# CheeseCake_1stAnn_SP.net
KiCad netlist of a schematic drawn in EasyEDA Pro
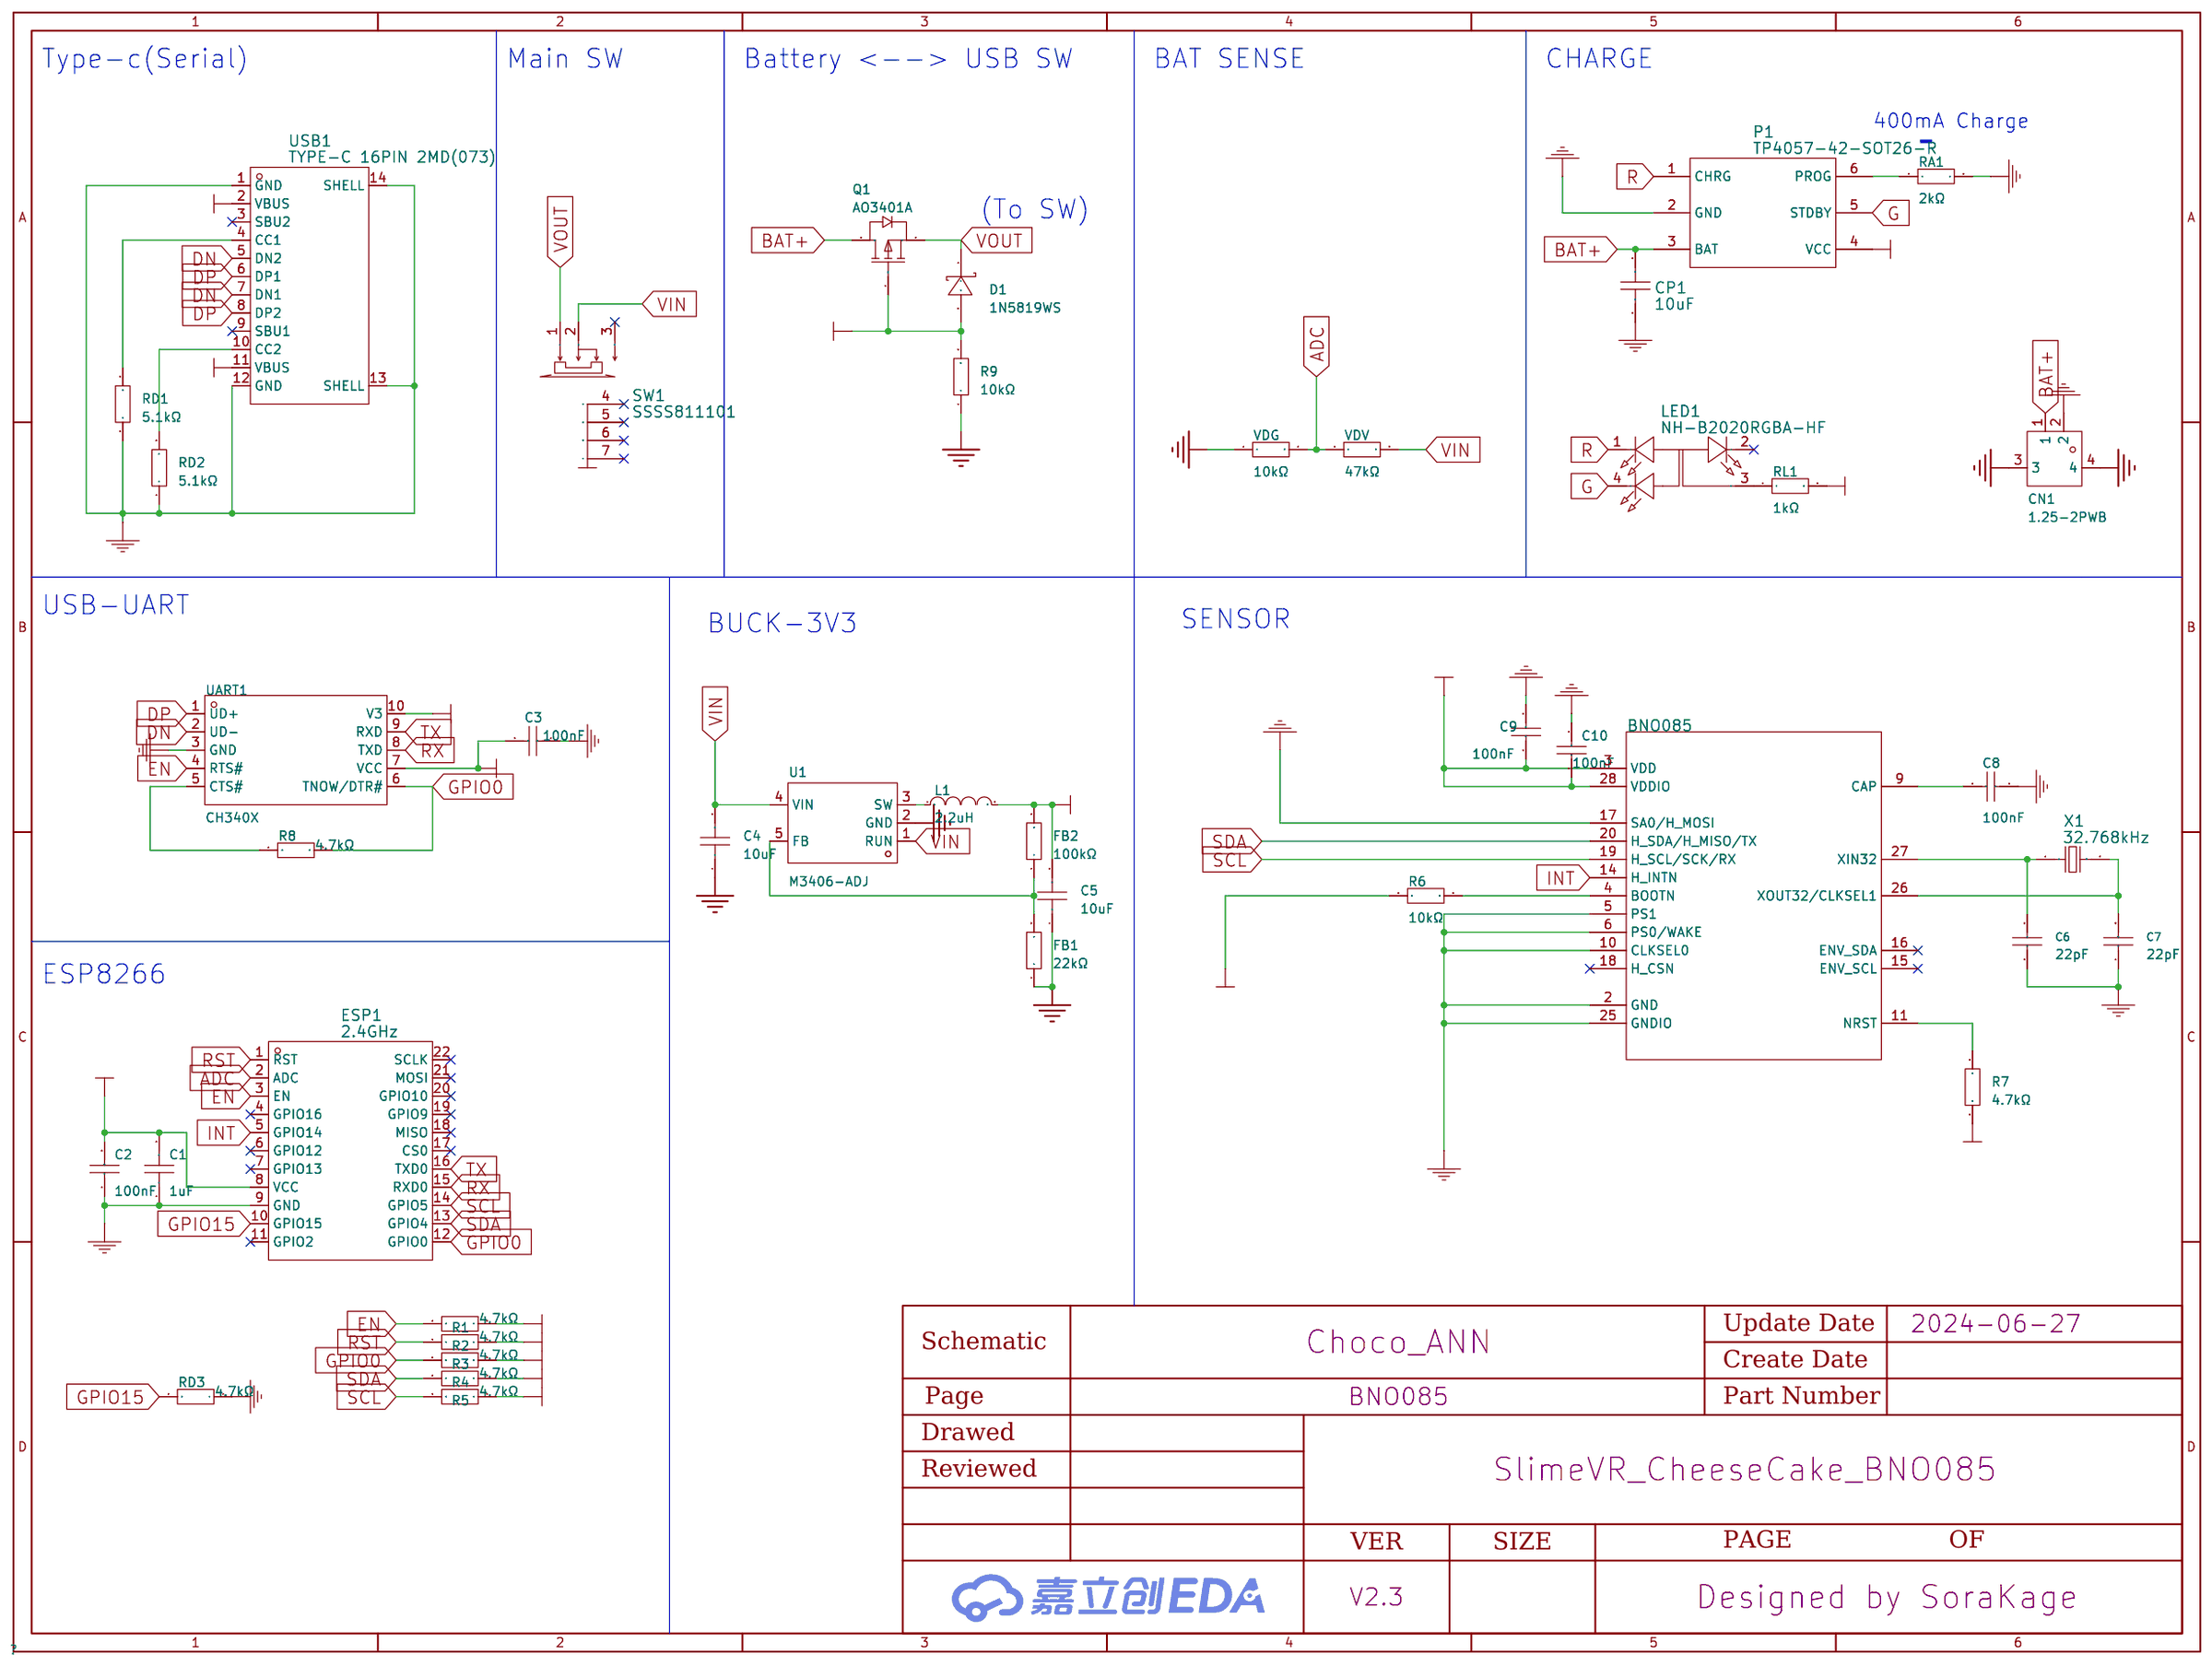
[diagram p0: schematic sheet]

(export (version "E")
  (design (tool "Eeschema 10.0.6"))
  (components
    (comp (ref "BNO085")
      (value "BNO080")
      (fields (field (name "Manufacturer Part") "BNO085") (field (name "Manufacturer") "Hillcrest"))
      (libsource (lib "easyedapro") (part "BNO080"))
    )
    (comp (ref "C1")
      (value "1uF")
      (footprint "easyedapro:C0402")
      (description "容值:1uF;精度:±10%;额定电压:25V;材质(温度系数):X5R;")
      (fields
        (field (name "Manufacturer Part") "CL05A105KA5NQNC")
        (field (name "Manufacturer") "SAMSUNG(三星)")
      )
      (libsource (lib "easyedapro") (part "CL05A105KA5NQNC"))
    )
    (comp (ref "C2")
      (value "100nF")
      (footprint "easyedapro:C0402")
      (description "容值:100nF;精度:±10%;额定电压:16V;材质(温度系数):X7R;")
      (fields
        (field (name "Manufacturer Part") "CL05B104KO5NNNC")
        (field (name "Manufacturer") "SAMSUNG(三星)")
      )
      (libsource (lib "easyedapro") (part "CL05B104KO5NNNC"))
    )
    (comp (ref "C3")
      (value "100nF")
      (footprint "easyedapro:C0402")
      (description "容值:100nF;精度:±10%;额定电压:16V;材质(温度系数):X7R;")
      (fields
        (field (name "Manufacturer Part") "CL05B104KO5NNNC")
        (field (name "Manufacturer") "SAMSUNG(三星)")
      )
      (libsource (lib "easyedapro") (part "CL05B104KO5NNNC"))
    )
    (comp (ref "C4")
      (value "10uF")
      (footprint "easyedapro:C0603")
      (description "容值:10uF;精度:±10%;额定电压:10V;材质(温度系数):X5R;")
      (fields
        (field (name "Manufacturer Part") "CL10A106KP8NNNC")
        (field (name "Manufacturer") "SAMSUNG(三星)")
      )
      (libsource (lib "easyedapro") (part "CL10A106KP8NNNC"))
    )
    (comp (ref "C5")
      (value "10uF")
      (footprint "easyedapro:C0603")
      (description "容值:10uF;精度:±10%;额定电压:10V;材质(温度系数):X5R;")
      (fields
        (field (name "Manufacturer Part") "CL10A106KP8NNNC")
        (field (name "Manufacturer") "SAMSUNG(三星)")
      )
      (libsource (lib "easyedapro") (part "CL10A106KP8NNNC"))
    )
    (comp (ref "C6")
      (value "22pF")
      (footprint "easyedapro:C0402")
      (description "容值:22pF;精度:±5%;额定电压:50V;材质(温度系数):C0G;")
      (fields (field (name "Manufacturer Part") "0402CG220J500NT") (field (name "Manufacturer") "FH(风华)"))
      (libsource (lib "easyedapro") (part "0402CG220J500NT"))
    )
    (comp (ref "C7")
      (value "22pF")
      (footprint "easyedapro:C0402")
      (description "容值:22pF;精度:±5%;额定电压:50V;材质(温度系数):C0G;")
      (fields (field (name "Manufacturer Part") "0402CG220J500NT") (field (name "Manufacturer") "FH(风华)"))
      (libsource (lib "easyedapro") (part "0402CG220J500NT"))
    )
    (comp (ref "C8")
      (value "100nF")
      (footprint "easyedapro:C0402")
      (description "容值:100nF;精度:±10%;额定电压:16V;材质(温度系数):X7R;")
      (fields
        (field (name "Manufacturer Part") "CL05B104KO5NNNC")
        (field (name "Manufacturer") "SAMSUNG(三星)")
      )
      (libsource (lib "easyedapro") (part "CL05B104KO5NNNC"))
    )
    (comp (ref "C9")
      (value "100nF")
      (footprint "easyedapro:C0402")
      (description "容值:100nF;精度:±10%;额定电压:16V;材质(温度系数):X7R;")
      (fields
        (field (name "Manufacturer Part") "CL05B104KO5NNNC")
        (field (name "Manufacturer") "SAMSUNG(三星)")
      )
      (libsource (lib "easyedapro") (part "CL05B104KO5NNNC"))
    )
    (comp (ref "C10")
      (value "100nF")
      (footprint "easyedapro:C0402")
      (description "容值:100nF;精度:±10%;额定电压:16V;材质(温度系数):X7R;")
      (fields
        (field (name "Manufacturer Part") "CL05B104KO5NNNC")
        (field (name "Manufacturer") "SAMSUNG(三星)")
      )
      (libsource (lib "easyedapro") (part "CL05B104KO5NNNC"))
    )
    (comp (ref "CN1")
      (value "1.25-2PWB")
      (footprint "easyedapro:CONN-SMD_2P-P1.25_DEALON_1.25-2PWB")
      (description "插针结构:1x2P;间距:1.25mm;安装方式:卧贴;参考系列:-;总PIN数:2P;排数:1;每排PIN数:2;行距:-;额定电流:-;工作温度范围:-40°C~+85°C;")
      (fields (field (name "Manufacturer") "DEALON(德艺隆)"))
      (libsource (lib "easyedapro") (part "1.25-2PWB"))
    )
    (comp (ref "CP1")
      (value "10uF")
      (footprint "easyedapro:C0603")
      (fields
        (field (name "Manufacturer Part") "CL10A106KP8NNNC")
        (field (name "Manufacturer") "SAMSUNG(三星)")
      )
      (libsource (lib "easyedapro") (part "10uF"))
    )
    (comp (ref "D1")
      (value "1N5819WS")
      (footprint "easyedapro:SOD-323_L1.8-W1.3-LS2.5-RD")
      (description "直流反向耐压(Vr):40V;平均整流电流(Io):1A;正向压降(Vf):600mV@1A;")
      (fields (field (name "Manufacturer") "Hottech(合科泰)"))
      (libsource (lib "easyedapro") (part "1N5819WS"))
    )
    (comp (ref "ESP1")
      (value "2.4GHz")
      (fields
        (field (name "Manufacturer Part") "ESP-12F(ESP8266MOD)")
        (field (name "Manufacturer") "Ai-Thinker(安信可)")
      )
      (libsource (lib "easyedapro") (part "ESP-12F(ESP8266MOD)"))
    )
    (comp (ref "FB1")
      (value "22kΩ")
      (footprint "easyedapro:R0402")
      (description "电阻类型:厚膜电阻;阻值:22kΩ;精度:±1%;功率:62.5mW;")
      (fields
        (field (name "Manufacturer Part") "0402WGF2202TCE")
        (field (name "Manufacturer") "UNI-ROYAL(厚声)")
      )
      (libsource (lib "easyedapro") (part "0402WGF2202TCE"))
    )
    (comp (ref "FB2")
      (value "100kΩ")
      (footprint "easyedapro:R0402")
      (description "电阻类型:厚膜电阻;阻值:100kΩ;精度:±1%;功率:62.5mW;")
      (fields
        (field (name "Manufacturer Part") "0402WGF1003TCE")
        (field (name "Manufacturer") "UNI-ROYAL(厚声)")
      )
      (libsource (lib "easyedapro") (part "0402WGF1003TCE"))
    )
    (comp (ref "L1")
      (value "2.2uH")
      (footprint "easyedapro:IND-SMD_L2.5-W2.0_YXMBL252010P")
      (description "类型:一体成型电感;电感值:2.2uH;精度:±20%;额定电流:2.1A;饱和电流(Isat):3A;")
      (fields (field (name "Manufacturer Part") "APH252010T2R2M") (field (name "Manufacturer") "APV(爱普微)"))
      (libsource (lib "easyedapro") (part "APH252010T2R2M"))
    )
    (comp (ref "LED1")
      (value "NH-B2020RGBA-HF")
      (footprint "easyedapro:LED-ARRAY-SMD_4P-L2.1-W2.1-TL_NH-B2020RGBA")
      (fields (field (name "Manufacturer") "国星光电"))
      (libsource (lib "easyedapro") (part "NH-B2020RGBA-HF"))
    )
    (comp (ref "P1")
      (value "TP4057-42-SOT26-R")
      (fields (field (name "Manufacturer") "TOPPOWER(南京拓微)"))
      (libsource (lib "easyedapro") (part "TP4057"))
    )
    (comp (ref "Q1")
      (value "AO3401A")
      (footprint "easyedapro:SOT-23_L2.9-W1.3-P1.90-LS2.4-BR")
      (description "类型:P沟道;漏源电压(Vdss):30V;连续漏极电流(Id):4A;功率(Pd):1.4W;导通电阻(RDS(on)@Vgs,Id):44mΩ@10V,4.3A;")
      (fields (field (name "Manufacturer") "AOS"))
      (libsource (lib "easyedapro") (part "AO3401A"))
    )
    (comp (ref "R1")
      (value "4.7kΩ")
      (footprint "easyedapro:R0402")
      (description "电阻类型:厚膜电阻;阻值:4.7kΩ;精度:±1%;功率:62.5mW;")
      (fields
        (field (name "Manufacturer Part") "0402WGF4701TCE")
        (field (name "Manufacturer") "UNI-ROYAL(厚声)")
      )
      (libsource (lib "easyedapro") (part "0402WGF4701TCE"))
    )
    (comp (ref "R2")
      (value "4.7kΩ")
      (footprint "easyedapro:R0402")
      (description "电阻类型:厚膜电阻;阻值:4.7kΩ;精度:±1%;功率:62.5mW;")
      (fields
        (field (name "Manufacturer Part") "0402WGF4701TCE")
        (field (name "Manufacturer") "UNI-ROYAL(厚声)")
      )
      (libsource (lib "easyedapro") (part "0402WGF4701TCE"))
    )
    (comp (ref "R3")
      (value "4.7kΩ")
      (footprint "easyedapro:R0402")
      (description "电阻类型:厚膜电阻;阻值:4.7kΩ;精度:±1%;功率:62.5mW;")
      (fields
        (field (name "Manufacturer Part") "0402WGF4701TCE")
        (field (name "Manufacturer") "UNI-ROYAL(厚声)")
      )
      (libsource (lib "easyedapro") (part "0402WGF4701TCE"))
    )
    (comp (ref "R4")
      (value "4.7kΩ")
      (footprint "easyedapro:R0402")
      (description "电阻类型:厚膜电阻;阻值:4.7kΩ;精度:±1%;功率:62.5mW;")
      (fields
        (field (name "Manufacturer Part") "0402WGF4701TCE")
        (field (name "Manufacturer") "UNI-ROYAL(厚声)")
      )
      (libsource (lib "easyedapro") (part "0402WGF4701TCE"))
    )
    (comp (ref "R5")
      (value "4.7kΩ")
      (footprint "easyedapro:R0402")
      (description "电阻类型:厚膜电阻;阻值:4.7kΩ;精度:±1%;功率:62.5mW;")
      (fields
        (field (name "Manufacturer Part") "0402WGF4701TCE")
        (field (name "Manufacturer") "UNI-ROYAL(厚声)")
      )
      (libsource (lib "easyedapro") (part "0402WGF4701TCE"))
    )
    (comp (ref "R6")
      (value "10kΩ")
      (footprint "easyedapro:R0402")
      (description "电阻类型:厚膜电阻;阻值:10kΩ;精度:±1%;功率:62.5mW;")
      (fields
        (field (name "Manufacturer Part") "0402WGF1002TCE")
        (field (name "Manufacturer") "UNI-ROYAL(厚声)")
      )
      (libsource (lib "easyedapro") (part "0402WGF1002TCE"))
    )
    (comp (ref "R7")
      (value "4.7kΩ")
      (footprint "easyedapro:R0402")
      (description "电阻类型:厚膜电阻;阻值:4.7kΩ;精度:±1%;功率:62.5mW;")
      (fields
        (field (name "Manufacturer Part") "0402WGF4701TCE")
        (field (name "Manufacturer") "UNI-ROYAL(厚声)")
      )
      (libsource (lib "easyedapro") (part "0402WGF4701TCE"))
    )
    (comp (ref "R8")
      (value "4.7kΩ")
      (footprint "easyedapro:R0402")
      (description "电阻类型:厚膜电阻;阻值:4.7kΩ;精度:±1%;功率:62.5mW;")
      (fields
        (field (name "Manufacturer Part") "0402WGF4701TCE")
        (field (name "Manufacturer") "UNI-ROYAL(厚声)")
      )
      (libsource (lib "easyedapro") (part "0402WGF4701TCE"))
    )
    (comp (ref "R9")
      (value "10kΩ")
      (footprint "easyedapro:R0402")
      (description "电阻类型:厚膜电阻;阻值:10kΩ;精度:±1%;功率:62.5mW;")
      (fields
        (field (name "Manufacturer Part") "0402WGF1002TCE")
        (field (name "Manufacturer") "UNI-ROYAL(厚声)")
      )
      (libsource (lib "easyedapro") (part "0402WGF1002TCE"))
    )
    (comp (ref "RA1")
      (value "2kΩ")
      (footprint "easyedapro:R0402")
      (description "电阻类型:厚膜电阻;阻值:2kΩ;精度:±1%;功率:62.5mW;")
      (fields
        (field (name "Manufacturer Part") "0402WGF2001TCE")
        (field (name "Manufacturer") "UNI-ROYAL(厚声)")
      )
      (libsource (lib "easyedapro") (part "0402WGF2001TCE"))
    )
    (comp (ref "RD1")
      (value "5.1kΩ")
      (footprint "easyedapro:R0402")
      (description "电阻类型:厚膜电阻;阻值:5.1kΩ;精度:±1%;功率:62.5mW;")
      (fields
        (field (name "Manufacturer Part") "0402WGF5101TCE")
        (field (name "Manufacturer") "UNI-ROYAL(厚声)")
      )
      (libsource (lib "easyedapro") (part "0402WGF5101TCE"))
    )
    (comp (ref "RD2")
      (value "5.1kΩ")
      (footprint "easyedapro:R0402")
      (description "电阻类型:厚膜电阻;阻值:5.1kΩ;精度:±1%;功率:62.5mW;")
      (fields
        (field (name "Manufacturer Part") "0402WGF5101TCE")
        (field (name "Manufacturer") "UNI-ROYAL(厚声)")
      )
      (libsource (lib "easyedapro") (part "0402WGF5101TCE"))
    )
    (comp (ref "RD3")
      (value "4.7kΩ")
      (footprint "easyedapro:R0402")
      (description "电阻类型:厚膜电阻;阻值:4.7kΩ;精度:±1%;功率:62.5mW;")
      (fields
        (field (name "Manufacturer Part") "0402WGF4701TCE")
        (field (name "Manufacturer") "UNI-ROYAL(厚声)")
      )
      (libsource (lib "easyedapro") (part "0402WGF4701TCE"))
    )
    (comp (ref "RL1")
      (value "1kΩ")
      (footprint "easyedapro:R0402")
      (description "电阻类型:厚膜电阻;阻值:1kΩ;精度:±1%;功率:62.5mW;")
      (fields
        (field (name "Manufacturer Part") "0402WGF1001TCE")
        (field (name "Manufacturer") "UNI-ROYAL(厚声)")
      )
      (libsource (lib "easyedapro") (part "0402WGF1001TCE"))
    )
    (comp (ref "SW1")
      (value "SSSS811101")
      (footprint "easyedapro:SW-SMD_SSSS811101")
      (fields (field (name "Manufacturer") "ALPSALPINE(阿尔卑斯阿尔派)"))
      (libsource (lib "easyedapro") (part "SSSS811101"))
    )
    (comp (ref "U1")
      (value "M3406-ADJ")
      (footprint "easyedapro:SOT-23-5_L3.0-W1.7-P0.95-LS2.8-BR")
      (description "功能类型:降压型;同步整流:-;输出通道数:-;拓扑结构:-;输入电压:-;输出电流(最大值):-;开关频率:-;")
      (fields (field (name "Manufacturer") "西安航天民芯"))
      (libsource (lib "easyedapro") (part "M3406"))
    )
    (comp (ref "UART1")
      (value "CH340X")
      (footprint "easyedapro:MSOP-10_L3.0-W3.0-P0.50-LS5.0-BL")
      (fields (field (name "Manufacturer") "WCH(南京沁恒)"))
      (libsource (lib "easyedapro") (part "CH340X"))
    )
    (comp (ref "USB1")
      (value "TYPE-C 16PIN 2MD(073)")
      (footprint "easyedapro:USB-C-SMD_TYPE-C-6PIN-2MD-073")
      (fields (field (name "Manufacturer") "SHOU HAN(首韩)"))
      (libsource (lib "easyedapro") (part "TYPE-C 16PIN 2MD(073)"))
    )
    (comp (ref "VDG")
      (value "10kΩ")
      (footprint "easyedapro:R0402")
      (description "电阻类型:厚膜电阻;阻值:10kΩ;精度:±1%;功率:62.5mW;")
      (fields
        (field (name "Manufacturer Part") "0402WGF1002TCE")
        (field (name "Manufacturer") "UNI-ROYAL(厚声)")
      )
      (libsource (lib "easyedapro") (part "0402WGF1002TCE"))
    )
    (comp (ref "VDV")
      (value "47kΩ")
      (footprint "easyedapro:R0402")
      (description "电阻类型:厚膜电阻;阻值:47kΩ;精度:±1%;功率:62.5mW;")
      (fields
        (field (name "Manufacturer Part") "0402WGF4702TCE")
        (field (name "Manufacturer") "UNI-ROYAL(厚声)")
      )
      (libsource (lib "easyedapro") (part "0402WGF4702TCE"))
    )
    (comp (ref "X1")
      (value "32.768kHz")
      (fields (field (name "Manufacturer Part") "Q13FC1350000400") (field (name "Manufacturer") "EPSON(爱普生)"))
      (libsource (lib "easyedapro") (part "32.768kHz"))
    )
  )
  (nets
    (net (code "1") (name "+5V") (class "Default")
      (node (ref "D1") (pin "2") (pinfunction "A_2") (pintype "unspecified"))
      (node (ref "P1") (pin "4") (pinfunction "VCC_4") (pintype "input"))
      (node (ref "Q1") (pin "1") (pinfunction "G_1") (pintype "input"))
      (node (ref "R9") (pin "2") (pinfunction "2_2") (pintype "input"))
      (node (ref "RL1") (pin "2") (pinfunction "2_2") (pintype "input"))
      (node (ref "USB1") (pin "11") (pinfunction "VBUS_11") (pintype "input"))
      (node (ref "USB1") (pin "2") (pinfunction "VBUS_2") (pintype "input"))
    )
    (net (code "2") (name "3V3") (class "Default")
      (node (ref "BNO085") (pin "28") (pinfunction "VDDIO_28") (pintype "input"))
      (node (ref "BNO085") (pin "3") (pinfunction "VDD_3") (pintype "input"))
      (node (ref "C1") (pin "2") (pinfunction "2_2") (pintype "unspecified"))
      (node (ref "C10") (pin "2") (pinfunction "2_2") (pintype "input"))
      (node (ref "C2") (pin "2") (pinfunction "2_2") (pintype "input"))
      (node (ref "C3") (pin "2") (pinfunction "2_2") (pintype "input"))
      (node (ref "C5") (pin "2") (pinfunction "2_2") (pintype "unspecified"))
      (node (ref "C9") (pin "2") (pinfunction "2_2") (pintype "input"))
      (node (ref "ESP1") (pin "8") (pinfunction "VCC_8") (pintype "input"))
      (node (ref "FB2") (pin "2") (pinfunction "2_2") (pintype "input"))
      (node (ref "L1") (pin "2") (pinfunction "2_2") (pintype "unspecified"))
      (node (ref "R1") (pin "1") (pinfunction "1_1") (pintype "input"))
      (node (ref "R2") (pin "1") (pinfunction "1_1") (pintype "input"))
      (node (ref "R3") (pin "1") (pinfunction "1_1") (pintype "input"))
      (node (ref "R4") (pin "1") (pinfunction "1_1") (pintype "input"))
      (node (ref "R5") (pin "1") (pinfunction "1_1") (pintype "input"))
      (node (ref "R6") (pin "1") (pinfunction "1_1") (pintype "input"))
      (node (ref "R7") (pin "2") (pinfunction "2_2") (pintype "input"))
      (node (ref "UART1") (pin "10") (pinfunction "V3_10") (pintype "unspecified"))
      (node (ref "UART1") (pin "7") (pinfunction "VCC_7") (pintype "unspecified"))
    )
    (net (code "3") (name "ADC") (class "Default")
      (node (ref "ESP1") (pin "2") (pinfunction "ADC_2") (pintype "input"))
      (node (ref "VDG") (pin "2") (pinfunction "2_2") (pintype "input"))
      (node (ref "VDV") (pin "1") (pinfunction "1_1") (pintype "input"))
    )
    (net (code "4") (name "BAT+") (class "Default")
      (node (ref "CN1") (pin "1") (pinfunction "1_1") (pintype "unspecified"))
      (node (ref "CP1") (pin "2") (pinfunction "2_2") (pintype "input"))
      (node (ref "P1") (pin "3") (pinfunction "BAT_3") (pintype "input"))
      (node (ref "Q1") (pin "3") (pinfunction "D_3") (pintype "input"))
    )
    (net (code "5") (name "DN") (class "Default")
      (node (ref "UART1") (pin "2") (pinfunction "UD-_2") (pintype "unspecified"))
      (node (ref "USB1") (pin "5") (pinfunction "DN2_5") (pintype "input"))
      (node (ref "USB1") (pin "7") (pinfunction "DN1_7") (pintype "input"))
    )
    (net (code "6") (name "DP") (class "Default")
      (node (ref "UART1") (pin "1") (pinfunction "UD+_1") (pintype "unspecified"))
      (node (ref "USB1") (pin "6") (pinfunction "DP1_6") (pintype "input"))
      (node (ref "USB1") (pin "8") (pinfunction "DP2_8") (pintype "input"))
    )
    (net (code "7") (name "EN") (class "Default")
      (node (ref "ESP1") (pin "3") (pinfunction "EN_3") (pintype "input"))
      (node (ref "R1") (pin "2") (pinfunction "2_2") (pintype "input"))
      (node (ref "UART1") (pin "4") (pinfunction "RTS#_4") (pintype "unspecified"))
    )
    (net (code "8") (name "G") (class "Default")
      (node (ref "LED1") (pin "4") (pinfunction "-_4") (pintype "input"))
      (node (ref "P1") (pin "5") (pinfunction "STDBY_5") (pintype "input"))
    )
    (net (code "9") (name "GND") (class "Default")
      (node (ref "BNO085") (pin "10") (pinfunction "CLKSEL0_10") (pintype "input"))
      (node (ref "BNO085") (pin "17") (pinfunction "SA0/H_MOSI_17") (pintype "input"))
      (node (ref "BNO085") (pin "2") (pinfunction "GND_2") (pintype "input"))
      (node (ref "BNO085") (pin "25") (pinfunction "GNDIO_25") (pintype "input"))
      (node (ref "BNO085") (pin "5") (pinfunction "PS1_5") (pintype "input"))
      (node (ref "BNO085") (pin "6") (pinfunction "PS0/WAKE_6") (pintype "input"))
      (node (ref "C1") (pin "1") (pinfunction "1_1") (pintype "unspecified"))
      (node (ref "C10") (pin "1") (pinfunction "1_1") (pintype "input"))
      (node (ref "C2") (pin "1") (pinfunction "1_1") (pintype "input"))
      (node (ref "C3") (pin "1") (pinfunction "1_1") (pintype "input"))
      (node (ref "C4") (pin "1") (pinfunction "1_1") (pintype "unspecified"))
      (node (ref "C5") (pin "1") (pinfunction "1_1") (pintype "unspecified"))
      (node (ref "C6") (pin "1") (pinfunction "1_1") (pintype "input"))
      (node (ref "C7") (pin "1") (pinfunction "1_1") (pintype "input"))
      (node (ref "C8") (pin "2") (pinfunction "2_2") (pintype "input"))
      (node (ref "C9") (pin "1") (pinfunction "1_1") (pintype "input"))
      (node (ref "CN1") (pin "2") (pinfunction "2_2") (pintype "unspecified"))
      (node (ref "CN1") (pin "3") (pinfunction "3_3") (pintype "unspecified"))
      (node (ref "CN1") (pin "4") (pinfunction "4_4") (pintype "unspecified"))
      (node (ref "CP1") (pin "1") (pinfunction "1_1") (pintype "input"))
      (node (ref "ESP1") (pin "9") (pinfunction "GND_9") (pintype "input"))
      (node (ref "FB1") (pin "1") (pinfunction "1_1") (pintype "input"))
      (node (ref "P1") (pin "2") (pinfunction "GND_2") (pintype "input"))
      (node (ref "R9") (pin "1") (pinfunction "1_1") (pintype "input"))
      (node (ref "RA1") (pin "2") (pinfunction "2_2") (pintype "input"))
      (node (ref "RD1") (pin "1") (pinfunction "1_1") (pintype "input"))
      (node (ref "RD2") (pin "1") (pinfunction "1_1") (pintype "input"))
      (node (ref "RD3") (pin "1") (pinfunction "1_1") (pintype "input"))
      (node (ref "U1") (pin "2") (pinfunction "GND_2") (pintype "input"))
      (node (ref "UART1") (pin "3") (pinfunction "GND_3") (pintype "unspecified"))
      (node (ref "USB1") (pin "1") (pinfunction "GND_1") (pintype "input"))
      (node (ref "USB1") (pin "12") (pinfunction "GND_12") (pintype "input"))
      (node (ref "USB1") (pin "13") (pinfunction "SHELL_13") (pintype "input"))
      (node (ref "USB1") (pin "14") (pinfunction "SHELL_14") (pintype "input"))
      (node (ref "VDG") (pin "1") (pinfunction "1_1") (pintype "input"))
    )
    (net (code "10") (name "GPIO0") (class "Default")
      (node (ref "ESP1") (pin "12") (pinfunction "GPIO0_12") (pintype "input"))
      (node (ref "R3") (pin "2") (pinfunction "2_2") (pintype "input"))
      (node (ref "R8") (pin "1") (pinfunction "1_1") (pintype "input"))
      (node (ref "UART1") (pin "6") (pinfunction "TNOW/DTR#_6") (pintype "unspecified"))
    )
    (net (code "11") (name "GPIO15") (class "Default")
      (node (ref "ESP1") (pin "10") (pinfunction "GPIO15_10") (pintype "input"))
      (node (ref "RD3") (pin "2") (pinfunction "2_2") (pintype "input"))
    )
    (net (code "12") (name "INT") (class "Default")
      (node (ref "BNO085") (pin "14") (pinfunction "H_INTN_14") (pintype "input"))
      (node (ref "ESP1") (pin "5") (pinfunction "GPIO14_5") (pintype "input"))
    )
    (net (code "13") (name "Net-(BNO085-BOOTN)") (class "Default")
      (node (ref "BNO085") (pin "4") (pinfunction "BOOTN_4") (pintype "input"))
      (node (ref "R6") (pin "2") (pinfunction "2_2") (pintype "input"))
    )
    (net (code "14") (name "Net-(BNO085-CAP)") (class "Default")
      (node (ref "BNO085") (pin "9") (pinfunction "CAP_9") (pintype "input"))
      (node (ref "C8") (pin "1") (pinfunction "1_1") (pintype "input"))
    )
    (net (code "15") (name "Net-(BNO085-NRST)") (class "Default")
      (node (ref "BNO085") (pin "11") (pinfunction "NRST_11") (pintype "input"))
      (node (ref "R7") (pin "1") (pinfunction "1_1") (pintype "input"))
    )
    (net (code "16") (name "Net-(BNO085-XIN32)") (class "Default")
      (node (ref "BNO085") (pin "27") (pinfunction "XIN32_27") (pintype "input"))
      (node (ref "C6") (pin "2") (pinfunction "2_2") (pintype "input"))
      (node (ref "X1") (pin "1") (pinfunction "1_1") (pintype "input"))
    )
    (net (code "17") (name "Net-(BNO085-XOUT32{slash}CLKSEL1)") (class "Default")
      (node (ref "BNO085") (pin "26") (pinfunction "XOUT32/CLKSEL1_26") (pintype "input"))
      (node (ref "C7") (pin "2") (pinfunction "2_2") (pintype "input"))
      (node (ref "X1") (pin "2") (pinfunction "2_2") (pintype "input"))
    )
    (net (code "18") (name "Net-(LED1-+)") (class "Default")
      (node (ref "LED1") (pin "3") (pinfunction "+_3") (pintype "input"))
      (node (ref "RL1") (pin "1") (pinfunction "1_1") (pintype "input"))
    )
    (net (code "19") (name "Net-(P1-PROG)") (class "Default")
      (node (ref "P1") (pin "6") (pinfunction "PROG_6") (pintype "input"))
      (node (ref "RA1") (pin "1") (pinfunction "1_1") (pintype "input"))
    )
    (net (code "20") (name "Net-(U1-FB)") (class "Default")
      (node (ref "FB1") (pin "2") (pinfunction "2_2") (pintype "input"))
      (node (ref "FB2") (pin "1") (pinfunction "1_1") (pintype "input"))
      (node (ref "U1") (pin "5") (pinfunction "FB_5") (pintype "input"))
    )
    (net (code "21") (name "Net-(U1-SW)") (class "Default")
      (node (ref "L1") (pin "1") (pinfunction "1_1") (pintype "unspecified"))
      (node (ref "U1") (pin "3") (pinfunction "SW_3") (pintype "input"))
    )
    (net (code "22") (name "Net-(UART1-CTS#)") (class "Default")
      (node (ref "R8") (pin "2") (pinfunction "2_2") (pintype "input"))
      (node (ref "UART1") (pin "5") (pinfunction "CTS#_5") (pintype "unspecified"))
    )
    (net (code "23") (name "Net-(USB1-CC1)") (class "Default")
      (node (ref "RD1") (pin "2") (pinfunction "2_2") (pintype "input"))
      (node (ref "USB1") (pin "4") (pinfunction "CC1_4") (pintype "input"))
    )
    (net (code "24") (name "Net-(USB1-CC2)") (class "Default")
      (node (ref "RD2") (pin "2") (pinfunction "2_2") (pintype "input"))
      (node (ref "USB1") (pin "10") (pinfunction "CC2_10") (pintype "input"))
    )
    (net (code "25") (name "R") (class "Default")
      (node (ref "LED1") (pin "1") (pinfunction "-_1") (pintype "input"))
      (node (ref "P1") (pin "1") (pinfunction "CHRG_1") (pintype "input"))
    )
    (net (code "26") (name "RST") (class "Default")
      (node (ref "ESP1") (pin "1") (pinfunction "RST_1") (pintype "input"))
      (node (ref "R2") (pin "2") (pinfunction "2_2") (pintype "input"))
    )
    (net (code "27") (name "RX") (class "Default")
      (node (ref "ESP1") (pin "15") (pinfunction "RXD0_15") (pintype "input"))
      (node (ref "UART1") (pin "8") (pinfunction "TXD_8") (pintype "unspecified"))
    )
    (net (code "28") (name "SCL") (class "Default")
      (node (ref "BNO085") (pin "19") (pinfunction "H_SCL/SCK/RX_19") (pintype "input"))
      (node (ref "ESP1") (pin "14") (pinfunction "GPIO5_14") (pintype "input"))
      (node (ref "R5") (pin "2") (pinfunction "2_2") (pintype "input"))
    )
    (net (code "29") (name "SDA") (class "Default")
      (node (ref "BNO085") (pin "20") (pinfunction "H_SDA/H_MISO/TX_20") (pintype "input"))
      (node (ref "ESP1") (pin "13") (pinfunction "GPIO4_13") (pintype "input"))
      (node (ref "R4") (pin "2") (pinfunction "2_2") (pintype "input"))
    )
    (net (code "30") (name "TX") (class "Default")
      (node (ref "ESP1") (pin "16") (pinfunction "TXD0_16") (pintype "input"))
      (node (ref "UART1") (pin "9") (pinfunction "RXD_9") (pintype "unspecified"))
    )
    (net (code "31") (name "VIN") (class "Default")
      (node (ref "C4") (pin "2") (pinfunction "2_2") (pintype "unspecified"))
      (node (ref "SW1") (pin "2") (pinfunction "2_2") (pintype "input"))
      (node (ref "U1") (pin "1") (pinfunction "RUN_1") (pintype "input"))
      (node (ref "U1") (pin "4") (pinfunction "VIN_4") (pintype "input"))
      (node (ref "VDV") (pin "2") (pinfunction "2_2") (pintype "input"))
    )
    (net (code "32") (name "VOUT") (class "Default")
      (node (ref "D1") (pin "1") (pinfunction "K_1") (pintype "unspecified"))
      (node (ref "Q1") (pin "2") (pinfunction "S_2") (pintype "input"))
      (node (ref "SW1") (pin "1") (pinfunction "1_1") (pintype "input"))
    )
    (net (code "33") (name "unconnected-(BNO085-ENV_SCL-Pad15)") (class "Default")
      (node (ref "BNO085") (pin "15") (pinfunction "ENV_SCL_15") (pintype "input+no_connect"))
    )
    (net (code "34") (name "unconnected-(BNO085-ENV_SDA-Pad16)") (class "Default")
      (node (ref "BNO085") (pin "16") (pinfunction "ENV_SDA_16") (pintype "input+no_connect"))
    )
    (net (code "35") (name "unconnected-(BNO085-H_CSN-Pad18)") (class "Default")
      (node (ref "BNO085") (pin "18") (pinfunction "H_CSN_18") (pintype "input+no_connect"))
    )
    (net (code "36") (name "unconnected-(ESP1-CS0-Pad17)") (class "Default")
      (node (ref "ESP1") (pin "17") (pinfunction "CS0_17") (pintype "input+no_connect"))
    )
    (net (code "37") (name "unconnected-(ESP1-GPIO2-Pad11)") (class "Default")
      (node (ref "ESP1") (pin "11") (pinfunction "GPIO2_11") (pintype "input+no_connect"))
    )
    (net (code "38") (name "unconnected-(ESP1-GPIO9-Pad19)") (class "Default")
      (node (ref "ESP1") (pin "19") (pinfunction "GPIO9_19") (pintype "input+no_connect"))
    )
    (net (code "39") (name "unconnected-(ESP1-GPIO10-Pad20)") (class "Default")
      (node (ref "ESP1") (pin "20") (pinfunction "GPIO10_20") (pintype "input+no_connect"))
    )
    (net (code "40") (name "unconnected-(ESP1-GPIO12-Pad6)") (class "Default")
      (node (ref "ESP1") (pin "6") (pinfunction "GPIO12_6") (pintype "input+no_connect"))
    )
    (net (code "41") (name "unconnected-(ESP1-GPIO13-Pad7)") (class "Default")
      (node (ref "ESP1") (pin "7") (pinfunction "GPIO13_7") (pintype "input+no_connect"))
    )
    (net (code "42") (name "unconnected-(ESP1-GPIO16-Pad4)") (class "Default")
      (node (ref "ESP1") (pin "4") (pinfunction "GPIO16_4") (pintype "input+no_connect"))
    )
    (net (code "43") (name "unconnected-(ESP1-MISO-Pad18)") (class "Default")
      (node (ref "ESP1") (pin "18") (pinfunction "MISO_18") (pintype "input+no_connect"))
    )
    (net (code "44") (name "unconnected-(ESP1-MOSI-Pad21)") (class "Default")
      (node (ref "ESP1") (pin "21") (pinfunction "MOSI_21") (pintype "input+no_connect"))
    )
    (net (code "45") (name "unconnected-(ESP1-SCLK-Pad22)") (class "Default")
      (node (ref "ESP1") (pin "22") (pinfunction "SCLK_22") (pintype "input+no_connect"))
    )
    (net (code "46") (name "unconnected-(LED1---Pad2)") (class "Default")
      (node (ref "LED1") (pin "2") (pinfunction "-_2") (pintype "input+no_connect"))
    )
    (net (code "47") (name "unconnected-(SW1-Pad3)") (class "Default")
      (node (ref "SW1") (pin "3") (pinfunction "3_3") (pintype "input+no_connect"))
    )
    (net (code "48") (name "unconnected-(SW1-Pad4)") (class "Default")
      (node (ref "SW1") (pin "4") (pinfunction "4_4") (pintype "input+no_connect"))
    )
    (net (code "49") (name "unconnected-(SW1-Pad5)") (class "Default")
      (node (ref "SW1") (pin "5") (pinfunction "5_5") (pintype "input+no_connect"))
    )
    (net (code "50") (name "unconnected-(SW1-Pad6)") (class "Default")
      (node (ref "SW1") (pin "6") (pinfunction "6_6") (pintype "input+no_connect"))
    )
    (net (code "51") (name "unconnected-(SW1-Pad7)") (class "Default")
      (node (ref "SW1") (pin "7") (pinfunction "7_7") (pintype "input+no_connect"))
    )
    (net (code "52") (name "unconnected-(USB1-SBU1-Pad9)") (class "Default")
      (node (ref "USB1") (pin "9") (pinfunction "SBU1_9") (pintype "input+no_connect"))
    )
    (net (code "53") (name "unconnected-(USB1-SBU2-Pad3)") (class "Default")
      (node (ref "USB1") (pin "3") (pinfunction "SBU2_3") (pintype "input+no_connect"))
    )
  )
)
